# 12V_LS.net
KiCad netlist of a schematic drawn in Altium Designer
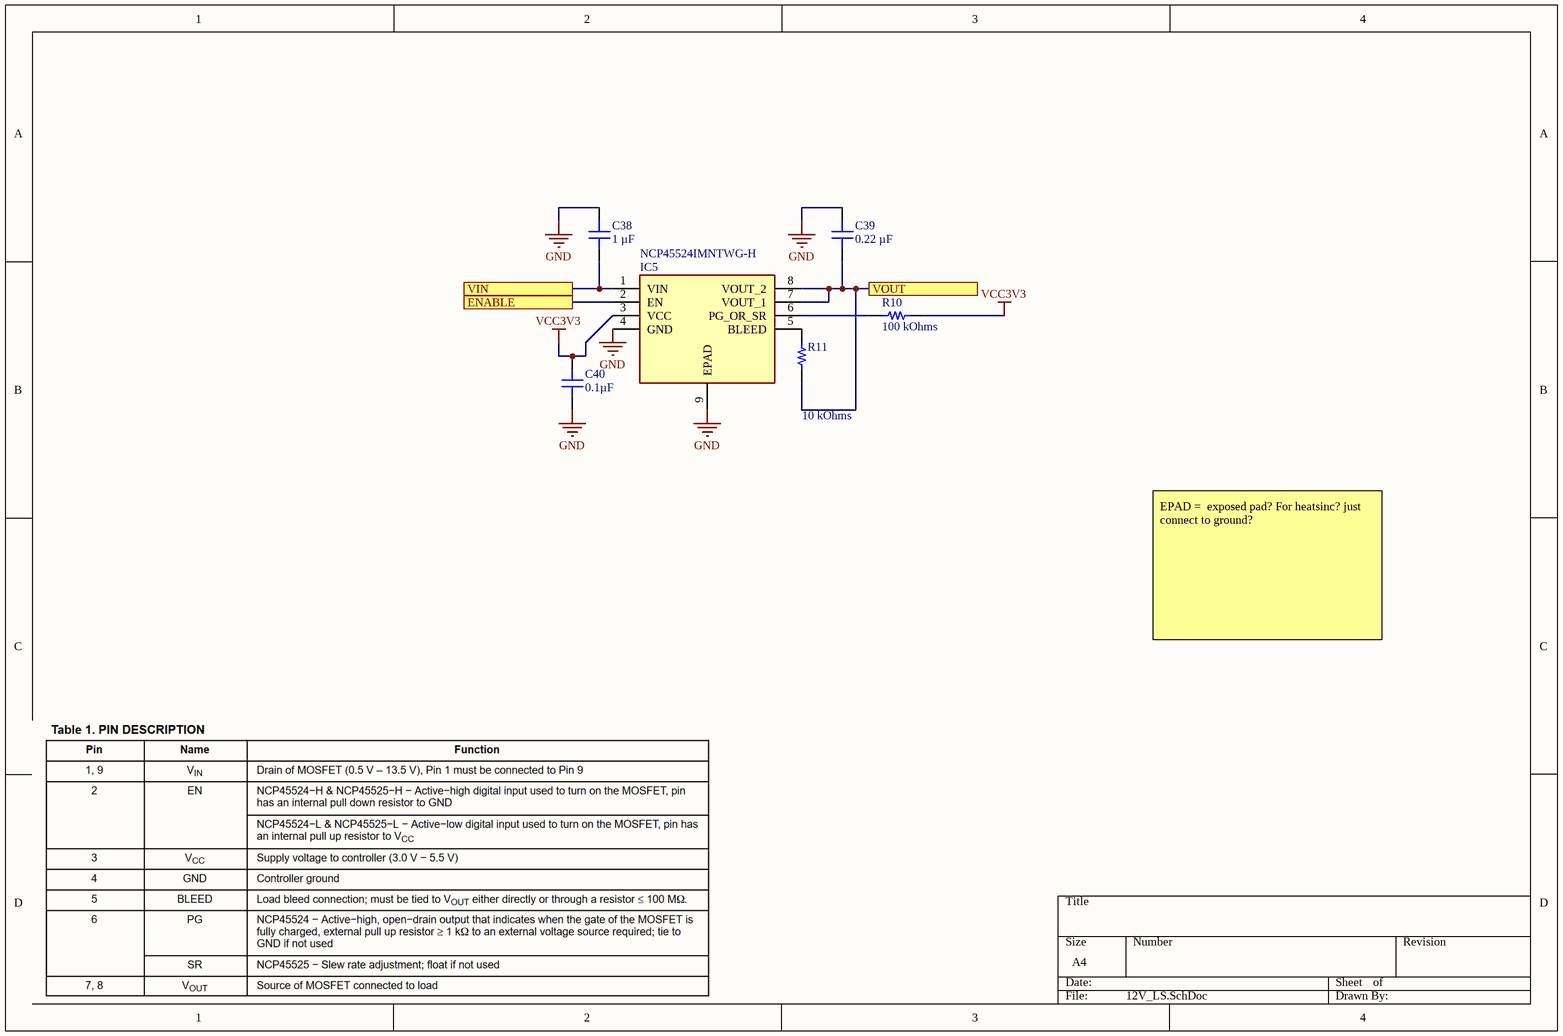
[diagram p0: 12V_LS.SchDoc]

(export (version "E")
  (design (tool "Eeschema 10.0.6"))
  (components
    (comp (ref "C38")
      (value "1 µF")
      (footprint "CAP 0402_1005")
      (description "CAP CER 1UF 10V X7S 0402")
      (fields
        (field (name "PART NUMBER") "GRM155C71A105KE11D")
        (field (name "MANUFACTURER") "Murata Electronics")
      )
      (libsource (lib "Celestial") (part "Capacitor"))
    )
    (comp (ref "C39")
      (value "0.22 µF")
      (footprint "CAP 0603_1608")
      (description "CAP CER 0.22UF 25V X7R 0603")
      (fields (field (name "PART NUMBER") "CC0603KRX7R8BB224") (field (name "MANUFACTURER") "Yageo"))
      (libsource (lib "Celestial Altium Library - altium_library") (part "Capacitor"))
    )
    (comp (ref "C40")
      (value "0.1µF")
      (footprint "CAP 0402_1005")
      (description "CAP CER 0.1UF 10V X7R 0402")
      (fields (field (name "PART NUMBER") "0402ZC104KAT2A") (field (name "MANUFACTURER") "AVX Corporation"))
      (libsource (lib "Celestial") (part "Capacitor"))
    )
    (comp (ref "IC5")
      (value "NCP45524IMNTWG-H")
      (footprint "SamacSys:SON50P200X200X100-9N")
      (description "Integrated Circuit")
      (fields (field (name "MOUSER PART NUMBER") "863-NCP45524IMNTWG-H"))
      (libsource (lib "*") (part "NCP45524IMNTWG-H"))
    )
    (comp (ref "R10")
      (value "100 kOhms")
      (footprint "RES 0603_1608")
      (description "RES 100K OHM 0.1% 1/16W 0603")
      (fields
        (field (name "PART NUMBER") "RNCS0603BKE100K")
        (field (name "MANUFACTURER") "Stackpole Electronics Inc")
      )
      (libsource (lib "Celestial Altium Library - altium_library") (part "Resistor"))
    )
    (comp (ref "R11")
      (value "10 kOhms")
      (footprint "RES 0603_1608")
      (description "RES 10K OHM 0.1% 1/16W 0603")
      (fields
        (field (name "PART NUMBER") "RNCS0603BKE10K0")
        (field (name "MANUFACTURER") "Stackpole Electronics Inc")
      )
      (libsource (lib "Celestial Altium Library - altium_library") (part "Resistor"))
    )
  )
  (nets
    (net (code "1") (name "/ENABLE") (class "Default")
      (node (ref "IC5") (pin "2") (pinfunction "EN_2") (pintype "passive"))
    )
    (net (code "2") (name "/VIN") (class "Default")
      (node (ref "C38") (pin "1") (pinfunction "1_1") (pintype "passive"))
      (node (ref "IC5") (pin "1") (pinfunction "VIN_1") (pintype "passive"))
    )
    (net (code "3") (name "/VOUT") (class "Default")
      (node (ref "C39") (pin "1") (pinfunction "1_1") (pintype "passive"))
      (node (ref "IC5") (pin "7") (pinfunction "VOUT_1_7") (pintype "passive"))
      (node (ref "IC5") (pin "8") (pinfunction "VOUT_2_8") (pintype "passive"))
      (node (ref "R11") (pin "1") (pinfunction "1_1") (pintype "passive"))
    )
    (net (code "4") (name "GND") (class "Default")
      (node (ref "C38") (pin "2") (pinfunction "2_2") (pintype "passive"))
      (node (ref "C39") (pin "2") (pinfunction "2_2") (pintype "passive"))
      (node (ref "C40") (pin "1") (pinfunction "1_1") (pintype "passive"))
      (node (ref "IC5") (pin "4") (pinfunction "GND_4") (pintype "passive"))
      (node (ref "IC5") (pin "9") (pinfunction "EPAD_9") (pintype "passive"))
    )
    (net (code "5") (name "Net-(IC5-BLEED)") (class "Default")
      (node (ref "IC5") (pin "5") (pinfunction "BLEED_5") (pintype "passive"))
      (node (ref "R11") (pin "2") (pinfunction "2_2") (pintype "passive"))
    )
    (net (code "6") (name "Net-(IC5-PG_OR_SR)") (class "Default")
      (node (ref "IC5") (pin "6") (pinfunction "PG_OR_SR_6") (pintype "passive"))
      (node (ref "R10") (pin "1") (pinfunction "1_1") (pintype "passive"))
    )
    (net (code "7") (name "VCC3V3") (class "Default")
      (node (ref "C40") (pin "2") (pinfunction "2_2") (pintype "passive"))
      (node (ref "IC5") (pin "3") (pinfunction "VCC_3") (pintype "passive"))
      (node (ref "R10") (pin "2") (pinfunction "2_2") (pintype "passive"))
    )
  )
)
